# Wiznet-W5500.net
KiCad netlist of a schematic drawn in EAGLE
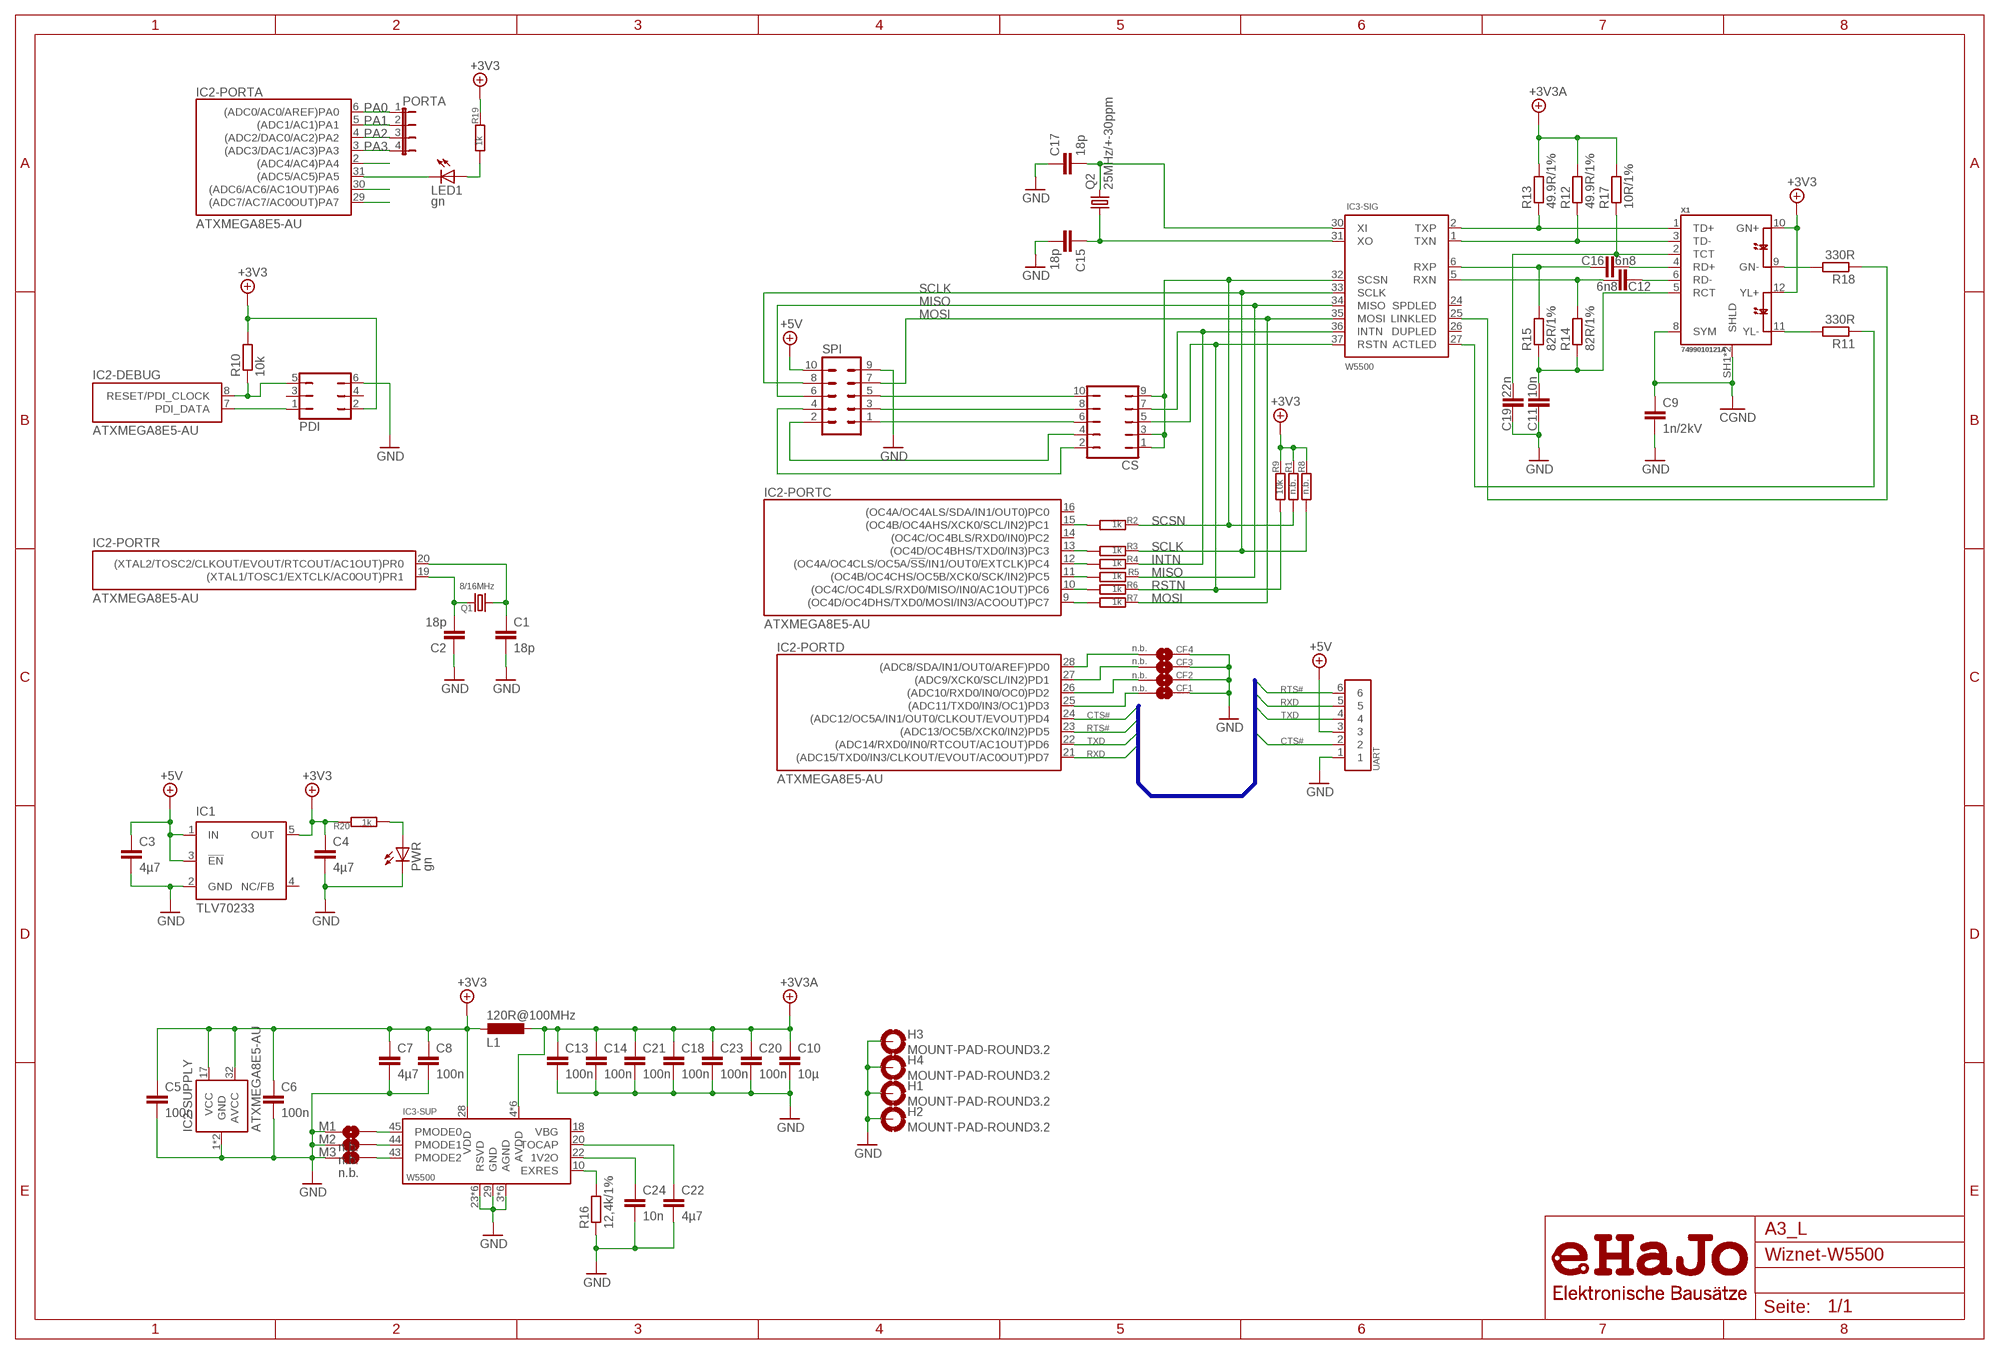
[diagram p0: schematic, sheet 1]

(export (version "E")
  (design (tool "Eeschema 10.0.6"))
  (components
    (comp (ref "C1")
      (value "18p")
      (footprint "eagle-import:C0603")
      (libsource (lib "eagle-import") (part "CC0603"))
    )
    (comp (ref "C2")
      (value "18p")
      (footprint "eagle-import:C0603")
      (libsource (lib "eagle-import") (part "CC0603"))
    )
    (comp (ref "C3")
      (value "4µ7")
      (footprint "eagle-import:C0805")
      (libsource (lib "eagle-import") (part "CC0805"))
    )
    (comp (ref "C4")
      (value "4µ7")
      (footprint "eagle-import:C0805")
      (libsource (lib "eagle-import") (part "CC0805"))
    )
    (comp (ref "C5")
      (value "100n")
      (footprint "eagle-import:C0603")
      (libsource (lib "eagle-import") (part "CC0603"))
    )
    (comp (ref "C6")
      (value "100n")
      (footprint "eagle-import:C0603")
      (libsource (lib "eagle-import") (part "CC0603"))
    )
    (comp (ref "C7")
      (value "4µ7")
      (footprint "eagle-import:C0805")
      (libsource (lib "eagle-import") (part "CC0805"))
    )
    (comp (ref "C8")
      (value "100n")
      (footprint "eagle-import:C0603")
      (libsource (lib "eagle-import") (part "CC0603"))
    )
    (comp (ref "C9")
      (value "1n/2kV")
      (footprint "eagle-import:C0805")
      (libsource (lib "eagle-import") (part "CC0805"))
    )
    (comp (ref "C10")
      (value "10µ")
      (footprint "eagle-import:C1206")
      (libsource (lib "eagle-import") (part "CC1206"))
    )
    (comp (ref "C11")
      (value "10n")
      (footprint "eagle-import:C0603")
      (libsource (lib "eagle-import") (part "CC0603"))
    )
    (comp (ref "C12")
      (value "6n8")
      (footprint "eagle-import:C0603")
      (libsource (lib "eagle-import") (part "CC0603"))
    )
    (comp (ref "C13")
      (value "100n")
      (footprint "eagle-import:C0603")
      (libsource (lib "eagle-import") (part "CC0603"))
    )
    (comp (ref "C14")
      (value "100n")
      (footprint "eagle-import:C0603")
      (libsource (lib "eagle-import") (part "CC0603"))
    )
    (comp (ref "C15")
      (value "18p")
      (footprint "eagle-import:C0603")
      (libsource (lib "eagle-import") (part "CC0603"))
    )
    (comp (ref "C16")
      (value "6n8")
      (footprint "eagle-import:C0603")
      (libsource (lib "eagle-import") (part "CC0603"))
    )
    (comp (ref "C17")
      (value "18p")
      (footprint "eagle-import:C0603")
      (libsource (lib "eagle-import") (part "CC0603"))
    )
    (comp (ref "C18")
      (value "100n")
      (footprint "eagle-import:C0603")
      (libsource (lib "eagle-import") (part "CC0603"))
    )
    (comp (ref "C19")
      (value "22n")
      (footprint "eagle-import:C0603")
      (libsource (lib "eagle-import") (part "CC0603"))
    )
    (comp (ref "C20")
      (value "100n")
      (footprint "eagle-import:C0603")
      (libsource (lib "eagle-import") (part "CC0603"))
    )
    (comp (ref "C21")
      (value "100n")
      (footprint "eagle-import:C0603")
      (libsource (lib "eagle-import") (part "CC0603"))
    )
    (comp (ref "C22")
      (value "4µ7")
      (footprint "eagle-import:C0805")
      (libsource (lib "eagle-import") (part "CC0805"))
    )
    (comp (ref "C23")
      (value "100n")
      (footprint "eagle-import:C0603")
      (libsource (lib "eagle-import") (part "CC0603"))
    )
    (comp (ref "C24")
      (value "10n")
      (footprint "eagle-import:C0603")
      (libsource (lib "eagle-import") (part "CC0603"))
    )
    (comp (ref "CF1")
      (value "n.b.")
      (footprint "eagle-import:SJS")
      (libsource (lib "eagle-import") (part "SJS"))
    )
    (comp (ref "CF2")
      (value "n.b.")
      (footprint "eagle-import:SJS")
      (libsource (lib "eagle-import") (part "SJS"))
    )
    (comp (ref "CF3")
      (value "n.b.")
      (footprint "eagle-import:SJS")
      (libsource (lib "eagle-import") (part "SJS"))
    )
    (comp (ref "CF4")
      (value "n.b.")
      (footprint "eagle-import:SJS")
      (libsource (lib "eagle-import") (part "SJS"))
    )
    (comp (ref "CS")
      (value "JP5Q")
      (footprint "eagle-import:JP5Q")
      (libsource (lib "eagle-import") (part "JP5Q"))
    )
    (comp (ref "H1")
      (value "MOUNT-PAD-ROUND3.2")
      (footprint "eagle-import:3,2-PAD")
      (libsource (lib "eagle-import") (part "MOUNT-PAD-ROUND3.2"))
    )
    (comp (ref "H2")
      (value "MOUNT-PAD-ROUND3.2")
      (footprint "eagle-import:3,2-PAD")
      (libsource (lib "eagle-import") (part "MOUNT-PAD-ROUND3.2"))
    )
    (comp (ref "H3")
      (value "MOUNT-PAD-ROUND3.2")
      (footprint "eagle-import:3,2-PAD")
      (libsource (lib "eagle-import") (part "MOUNT-PAD-ROUND3.2"))
    )
    (comp (ref "H4")
      (value "MOUNT-PAD-ROUND3.2")
      (footprint "eagle-import:3,2-PAD")
      (libsource (lib "eagle-import") (part "MOUNT-PAD-ROUND3.2"))
    )
    (comp (ref "IC1")
      (value "TLV70233")
      (footprint "eagle-import:SOT23-DBV")
      (libsource (lib "eagle-import") (part "TPS77001"))
    )
    (comp (ref "IC2")
      (value "ATXMEGA8E5-AU")
      (footprint "eagle-import:TQFP32-08")
      (libsource (lib "eagle-import") (part "ATXMEGAE5-AU"))
    )
    (comp (ref "IC3")
      (value "W5500")
      (footprint "eagle-import:LQFP48")
      (libsource (lib "eagle-import") (part "W5500"))
    )
    (comp (ref "L1")
      (value "120R@100MHz")
      (footprint "eagle-import:R0805")
      (libsource (lib "eagle-import") (part "L0805"))
    )
    (comp (ref "LED1")
      (value "gn")
      (footprint "eagle-import:CHIP-LED0805")
      (libsource (lib "eagle-import") (part "LEDCHIP-LED0805"))
    )
    (comp (ref "M1")
      (value "n.b.")
      (footprint "eagle-import:SJS")
      (libsource (lib "eagle-import") (part "SJS"))
    )
    (comp (ref "M2")
      (value "n.b.")
      (footprint "eagle-import:SJS")
      (libsource (lib "eagle-import") (part "SJS"))
    )
    (comp (ref "M3")
      (value "n.b.")
      (footprint "eagle-import:SJS")
      (libsource (lib "eagle-import") (part "SJS"))
    )
    (comp (ref "PDI")
      (value "JP3Q")
      (footprint "eagle-import:JP3Q")
      (libsource (lib "eagle-import") (part "JP3Q"))
    )
    (comp (ref "PORTA")
      (value "JP4ESML")
      (footprint "eagle-import:4SML")
      (libsource (lib "eagle-import") (part "JP4ESML"))
    )
    (comp (ref "PWR")
      (value "gn")
      (footprint "eagle-import:CHIP-LED0805")
      (libsource (lib "eagle-import") (part "LEDCHIP-LED0805"))
    )
    (comp (ref "Q1")
      (value "8/16MHz")
      (footprint "eagle-import:HC49U70")
      (libsource (lib "eagle-import") (part "CRYSTALHC49U70"))
    )
    (comp (ref "Q2")
      (value "25MHz/+-30ppm")
      (footprint "eagle-import:HC49U70")
      (libsource (lib "eagle-import") (part "CRYSTALHC49U70"))
    )
    (comp (ref "R1")
      (value "n.b.")
      (footprint "eagle-import:R0603")
      (libsource (lib "eagle-import") (part "RR0603"))
    )
    (comp (ref "R2")
      (value "1k")
      (footprint "eagle-import:R0603")
      (libsource (lib "eagle-import") (part "RR0603"))
    )
    (comp (ref "R3")
      (value "1k")
      (footprint "eagle-import:R0603")
      (libsource (lib "eagle-import") (part "RR0603"))
    )
    (comp (ref "R4")
      (value "1k")
      (footprint "eagle-import:R0603")
      (libsource (lib "eagle-import") (part "RR0603"))
    )
    (comp (ref "R5")
      (value "1k")
      (footprint "eagle-import:R0603")
      (libsource (lib "eagle-import") (part "RR0603"))
    )
    (comp (ref "R6")
      (value "1k")
      (footprint "eagle-import:R0603")
      (libsource (lib "eagle-import") (part "RR0603"))
    )
    (comp (ref "R7")
      (value "1k")
      (footprint "eagle-import:R0603")
      (libsource (lib "eagle-import") (part "RR0603"))
    )
    (comp (ref "R8")
      (value "n.b.")
      (footprint "eagle-import:R0603")
      (libsource (lib "eagle-import") (part "RR0603"))
    )
    (comp (ref "R9")
      (value "10k")
      (footprint "eagle-import:R0603")
      (libsource (lib "eagle-import") (part "RR0603"))
    )
    (comp (ref "R10")
      (value "10k")
      (footprint "eagle-import:R0603")
      (libsource (lib "eagle-import") (part "RR0603"))
    )
    (comp (ref "R11")
      (value "330R")
      (footprint "eagle-import:R0603")
      (libsource (lib "eagle-import") (part "RR0603"))
    )
    (comp (ref "R12")
      (value "49.9R/1%")
      (footprint "eagle-import:R0603")
      (libsource (lib "eagle-import") (part "RR0603"))
    )
    (comp (ref "R13")
      (value "49.9R/1%")
      (footprint "eagle-import:R0603")
      (libsource (lib "eagle-import") (part "RR0603"))
    )
    (comp (ref "R14")
      (value "82R/1%")
      (footprint "eagle-import:R0603")
      (libsource (lib "eagle-import") (part "RR0603"))
    )
    (comp (ref "R15")
      (value "82R/1%")
      (footprint "eagle-import:R0603")
      (libsource (lib "eagle-import") (part "RR0603"))
    )
    (comp (ref "R16")
      (value "12,4k/1%")
      (footprint "eagle-import:R0603")
      (libsource (lib "eagle-import") (part "RR0603"))
    )
    (comp (ref "R17")
      (value "10R/1%")
      (footprint "eagle-import:R0603")
      (libsource (lib "eagle-import") (part "RR0603"))
    )
    (comp (ref "R18")
      (value "330R")
      (footprint "eagle-import:R0603")
      (libsource (lib "eagle-import") (part "RR0603"))
    )
    (comp (ref "R19")
      (value "1k")
      (footprint "eagle-import:R0603")
      (libsource (lib "eagle-import") (part "RR0603"))
    )
    (comp (ref "R20")
      (value "1k")
      (footprint "eagle-import:R0603")
      (libsource (lib "eagle-import") (part "RR0603"))
    )
    (comp (ref "SPI")
      (value "ML10")
      (footprint "eagle-import:ML10")
      (libsource (lib "eagle-import") (part "ML10"))
    )
    (comp (ref "UART")
      (value "JP6E")
      (footprint "eagle-import:JP6E")
      (libsource (lib "eagle-import") (part "JP6E"))
    )
    (comp (ref "X1")
      (value "7499010121A")
      (footprint "eagle-import:121A")
      (libsource (lib "eagle-import") (part "7499010121"))
    )
  )
  (nets
    (net (code "1") (name "+3V3") (class "Default")
      (node (ref "C4") (pin "1") (pinfunction "1_1") (pintype "passive"))
      (node (ref "C5") (pin "1") (pinfunction "1_1") (pintype "passive"))
      (node (ref "C6") (pin "1") (pinfunction "1_1") (pintype "passive"))
      (node (ref "C7") (pin "1") (pinfunction "1_1") (pintype "passive"))
      (node (ref "C8") (pin "1") (pinfunction "1_1") (pintype "passive"))
      (node (ref "IC1") (pin "5") (pinfunction "OUT_5") (pintype "passive"))
      (node (ref "IC2") (pin "17") (pinfunction "VCC_17") (pintype "bidirectional"))
      (node (ref "IC2") (pin "32") (pinfunction "AVCC_32") (pintype "bidirectional"))
      (node (ref "IC3") (pin "28") (pinfunction "VDD_28") (pintype "power_in"))
      (node (ref "L1") (pin "2") (pinfunction "2_2") (pintype "passive"))
      (node (ref "PDI") (pin "2") (pinfunction "2_2") (pintype "passive"))
      (node (ref "R1") (pin "2") (pinfunction "2_2") (pintype "passive"))
      (node (ref "R10") (pin "2") (pinfunction "2_2") (pintype "passive"))
      (node (ref "R19") (pin "2") (pinfunction "2_2") (pintype "passive"))
      (node (ref "R20") (pin "2") (pinfunction "2_2") (pintype "passive"))
      (node (ref "R8") (pin "2") (pinfunction "2_2") (pintype "passive"))
      (node (ref "R9") (pin "2") (pinfunction "2_2") (pintype "passive"))
      (node (ref "X1") (pin "10") (pinfunction "GN+_10") (pintype "bidirectional"))
      (node (ref "X1") (pin "12") (pinfunction "YL+_12") (pintype "bidirectional"))
    )
    (net (code "2") (name "+3V3A") (class "Default")
      (node (ref "C10") (pin "1") (pinfunction "1_1") (pintype "passive"))
      (node (ref "C13") (pin "1") (pinfunction "1_1") (pintype "passive"))
      (node (ref "C14") (pin "1") (pinfunction "1_1") (pintype "passive"))
      (node (ref "C18") (pin "1") (pinfunction "1_1") (pintype "passive"))
      (node (ref "C20") (pin "1") (pinfunction "1_1") (pintype "passive"))
      (node (ref "C21") (pin "1") (pinfunction "1_1") (pintype "passive"))
      (node (ref "C23") (pin "1") (pinfunction "1_1") (pintype "passive"))
      (node (ref "IC3") (pin "11") (pinfunction "AVDD_11") (pintype "power_in"))
      (node (ref "IC3") (pin "15") (pinfunction "AVDD_15") (pintype "power_in"))
      (node (ref "IC3") (pin "17") (pinfunction "AVDD_17") (pintype "power_in"))
      (node (ref "IC3") (pin "21") (pinfunction "AVDD_21") (pintype "power_in"))
      (node (ref "IC3") (pin "4") (pinfunction "AVDD_4") (pintype "power_in"))
      (node (ref "IC3") (pin "8") (pinfunction "AVDD_8") (pintype "power_in"))
      (node (ref "L1") (pin "1") (pinfunction "1_1") (pintype "passive"))
      (node (ref "R12") (pin "2") (pinfunction "2_2") (pintype "passive"))
      (node (ref "R13") (pin "2") (pinfunction "2_2") (pintype "passive"))
      (node (ref "R17") (pin "2") (pinfunction "2_2") (pintype "passive"))
    )
    (net (code "3") (name "+5V") (class "Default")
      (node (ref "C3") (pin "1") (pinfunction "1_1") (pintype "passive"))
      (node (ref "IC1") (pin "1") (pinfunction "IN_1") (pintype "input"))
      (node (ref "IC1") (pin "3") (pinfunction "~{EN}_3") (pintype "input"))
      (node (ref "SPI") (pin "10") (pinfunction "10_10") (pintype "passive"))
      (node (ref "UART") (pin "3") (pinfunction "3_3") (pintype "bidirectional"))
    )
    (net (code "4") (name "/CTS#") (class "Default")
      (node (ref "IC2") (pin "24") (pinfunction "(ADC12/OC5A/IN1/OUT0/CLKOUT/EVOUT)PD4_24") (pintype "bidirectional"))
      (node (ref "UART") (pin "2") (pinfunction "2_2") (pintype "bidirectional"))
    )
    (net (code "5") (name "/INTN") (class "Default")
      (node (ref "CS") (pin "7") (pinfunction "7_7") (pintype "passive"))
      (node (ref "IC3") (pin "36") (pinfunction "INTN_36") (pintype "output"))
      (node (ref "R4") (pin "1") (pinfunction "1_1") (pintype "passive"))
    )
    (net (code "6") (name "/MISO") (class "Default")
      (node (ref "IC3") (pin "34") (pinfunction "MISO_34") (pintype "output"))
      (node (ref "R5") (pin "1") (pinfunction "1_1") (pintype "passive"))
      (node (ref "SPI") (pin "6") (pinfunction "6_6") (pintype "passive"))
    )
    (net (code "7") (name "/MOSI") (class "Default")
      (node (ref "IC3") (pin "35") (pinfunction "MOSI_35") (pintype "input"))
      (node (ref "R7") (pin "1") (pinfunction "1_1") (pintype "passive"))
      (node (ref "SPI") (pin "7") (pinfunction "7_7") (pintype "passive"))
    )
    (net (code "8") (name "/PA0") (class "Default")
      (node (ref "IC2") (pin "6") (pinfunction "(ADC0/AC0/AREF)PA0_6") (pintype "bidirectional"))
      (node (ref "PORTA") (pin "1") (pinfunction "1_1") (pintype "passive"))
    )
    (net (code "9") (name "/PA1") (class "Default")
      (node (ref "IC2") (pin "5") (pinfunction "(ADC1/AC1)PA1_5") (pintype "bidirectional"))
      (node (ref "PORTA") (pin "2") (pinfunction "2_2") (pintype "passive"))
    )
    (net (code "10") (name "/PA2") (class "Default")
      (node (ref "IC2") (pin "4") (pinfunction "(ADC2/DAC0/AC2)PA2_4") (pintype "bidirectional"))
      (node (ref "PORTA") (pin "3") (pinfunction "3_3") (pintype "passive"))
    )
    (net (code "11") (name "/PA3") (class "Default")
      (node (ref "IC2") (pin "3") (pinfunction "(ADC3/DAC1/AC3)PA3_3") (pintype "bidirectional"))
      (node (ref "PORTA") (pin "4") (pinfunction "4_4") (pintype "passive"))
    )
    (net (code "12") (name "/RSTN") (class "Default")
      (node (ref "CS") (pin "5") (pinfunction "5_5") (pintype "passive"))
      (node (ref "IC3") (pin "37") (pinfunction "RSTN_37") (pintype "input"))
      (node (ref "R6") (pin "1") (pinfunction "1_1") (pintype "passive"))
      (node (ref "R9") (pin "1") (pinfunction "1_1") (pintype "passive"))
    )
    (net (code "13") (name "/RTS#") (class "Default")
      (node (ref "IC2") (pin "23") (pinfunction "(ADC13/OC5B/XCK0/IN2)PD5_23") (pintype "bidirectional"))
      (node (ref "UART") (pin "6") (pinfunction "6_6") (pintype "bidirectional"))
    )
    (net (code "14") (name "/RXD") (class "Default")
      (node (ref "IC2") (pin "21") (pinfunction "(ADC15/TXD0/IN3/CLKOUT/EVOUT/AC0OUT)PD7_21") (pintype "bidirectional"))
      (node (ref "UART") (pin "5") (pinfunction "5_5") (pintype "bidirectional"))
    )
    (net (code "15") (name "/SCLK") (class "Default")
      (node (ref "IC3") (pin "33") (pinfunction "SCLK_33") (pintype "input"))
      (node (ref "R3") (pin "1") (pinfunction "1_1") (pintype "passive"))
      (node (ref "R8") (pin "1") (pinfunction "1_1") (pintype "passive"))
      (node (ref "SPI") (pin "8") (pinfunction "8_8") (pintype "passive"))
    )
    (net (code "16") (name "/SCSN") (class "Default")
      (node (ref "CS") (pin "1") (pinfunction "1_1") (pintype "passive"))
      (node (ref "CS") (pin "3") (pinfunction "3_3") (pintype "passive"))
      (node (ref "CS") (pin "9") (pinfunction "9_9") (pintype "passive"))
      (node (ref "IC3") (pin "32") (pinfunction "SCSN_32") (pintype "input"))
      (node (ref "R1") (pin "1") (pinfunction "1_1") (pintype "passive"))
      (node (ref "R2") (pin "1") (pinfunction "1_1") (pintype "passive"))
    )
    (net (code "17") (name "/TXD") (class "Default")
      (node (ref "IC2") (pin "22") (pinfunction "(ADC14/RXD0/IN0/RTCOUT/AC1OUT)PD6_22") (pintype "bidirectional"))
      (node (ref "UART") (pin "4") (pinfunction "4_4") (pintype "bidirectional"))
    )
    (net (code "18") (name "CGND") (class "Default")
      (node (ref "C9") (pin "1") (pinfunction "1_1") (pintype "passive"))
      (node (ref "X1") (pin "8") (pinfunction "SYM_8") (pintype "bidirectional"))
      (node (ref "X1") (pin "SH1") (pinfunction "SHLD_SH1") (pintype "bidirectional"))
      (node (ref "X1") (pin "SH2") (pinfunction "SHLD_SH2") (pintype "bidirectional"))
    )
    (net (code "19") (name "GND") (class "Default")
      (node (ref "C1") (pin "2") (pinfunction "2_2") (pintype "passive"))
      (node (ref "C10") (pin "2") (pinfunction "2_2") (pintype "passive"))
      (node (ref "C11") (pin "1") (pinfunction "1_1") (pintype "passive"))
      (node (ref "C13") (pin "2") (pinfunction "2_2") (pintype "passive"))
      (node (ref "C14") (pin "2") (pinfunction "2_2") (pintype "passive"))
      (node (ref "C15") (pin "2") (pinfunction "2_2") (pintype "passive"))
      (node (ref "C17") (pin "1") (pinfunction "1_1") (pintype "passive"))
      (node (ref "C18") (pin "2") (pinfunction "2_2") (pintype "passive"))
      (node (ref "C19") (pin "1") (pinfunction "1_1") (pintype "passive"))
      (node (ref "C2") (pin "1") (pinfunction "1_1") (pintype "passive"))
      (node (ref "C20") (pin "2") (pinfunction "2_2") (pintype "passive"))
      (node (ref "C21") (pin "2") (pinfunction "2_2") (pintype "passive"))
      (node (ref "C22") (pin "2") (pinfunction "2_2") (pintype "passive"))
      (node (ref "C23") (pin "2") (pinfunction "2_2") (pintype "passive"))
      (node (ref "C24") (pin "2") (pinfunction "2_2") (pintype "passive"))
      (node (ref "C3") (pin "2") (pinfunction "2_2") (pintype "passive"))
      (node (ref "C4") (pin "2") (pinfunction "2_2") (pintype "passive"))
      (node (ref "C5") (pin "2") (pinfunction "2_2") (pintype "passive"))
      (node (ref "C6") (pin "2") (pinfunction "2_2") (pintype "passive"))
      (node (ref "C7") (pin "2") (pinfunction "2_2") (pintype "passive"))
      (node (ref "C8") (pin "2") (pinfunction "2_2") (pintype "passive"))
      (node (ref "C9") (pin "2") (pinfunction "2_2") (pintype "passive"))
      (node (ref "CF1") (pin "2") (pinfunction "2_2") (pintype "passive"))
      (node (ref "CF2") (pin "2") (pinfunction "2_2") (pintype "passive"))
      (node (ref "CF3") (pin "2") (pinfunction "2_2") (pintype "passive"))
      (node (ref "CF4") (pin "2") (pinfunction "2_2") (pintype "passive"))
      (node (ref "H1") (pin "B3,2") (pinfunction "MOUNT_B3,2") (pintype "passive"))
      (node (ref "H2") (pin "B3,2") (pinfunction "MOUNT_B3,2") (pintype "passive"))
      (node (ref "H3") (pin "B3,2") (pinfunction "MOUNT_B3,2") (pintype "passive"))
      (node (ref "H4") (pin "B3,2") (pinfunction "MOUNT_B3,2") (pintype "passive"))
      (node (ref "IC1") (pin "2") (pinfunction "GND_2") (pintype "power_in"))
      (node (ref "IC2") (pin "1") (pinfunction "GND_1") (pintype "bidirectional"))
      (node (ref "IC2") (pin "18") (pinfunction "GND_18") (pintype "bidirectional"))
      (node (ref "IC3") (pin "14") (pinfunction "AGND_14") (pintype "power_in"))
      (node (ref "IC3") (pin "16") (pinfunction "AGND_16") (pintype "power_in"))
      (node (ref "IC3") (pin "19") (pinfunction "AGND_19") (pintype "power_in"))
      (node (ref "IC3") (pin "23") (pinfunction "RSVD_23") (pintype "input"))
      (node (ref "IC3") (pin "29") (pinfunction "GND_29") (pintype "power_in"))
      (node (ref "IC3") (pin "3") (pinfunction "AGND_3") (pintype "power_in"))
      (node (ref "IC3") (pin "38") (pinfunction "RSVD_38") (pintype "input"))
      (node (ref "IC3") (pin "39") (pinfunction "RSVD_39") (pintype "input"))
      (node (ref "IC3") (pin "40") (pinfunction "RSVD_40") (pintype "input"))
      (node (ref "IC3") (pin "41") (pinfunction "RSVD_41") (pintype "input"))
      (node (ref "IC3") (pin "42") (pinfunction "RSVD_42") (pintype "input"))
      (node (ref "IC3") (pin "48") (pinfunction "AGND_48") (pintype "power_in"))
      (node (ref "IC3") (pin "9") (pinfunction "AGND_9") (pintype "power_in"))
      (node (ref "M1") (pin "1") (pinfunction "1_1") (pintype "passive"))
      (node (ref "M2") (pin "1") (pinfunction "1_1") (pintype "passive"))
      (node (ref "M3") (pin "1") (pinfunction "1_1") (pintype "passive"))
      (node (ref "PDI") (pin "6") (pinfunction "6_6") (pintype "passive"))
      (node (ref "PWR") (pin "C") (pinfunction "C_C") (pintype "passive"))
      (node (ref "R16") (pin "1") (pinfunction "1_1") (pintype "passive"))
      (node (ref "SPI") (pin "9") (pinfunction "9_9") (pintype "passive"))
      (node (ref "UART") (pin "1") (pinfunction "1_1") (pintype "bidirectional"))
    )
    (net (code "20") (name "Net-(CS-Pad2)") (class "Default")
      (node (ref "CS") (pin "2") (pinfunction "2_2") (pintype "passive"))
      (node (ref "SPI") (pin "4") (pinfunction "4_4") (pintype "passive"))
    )
    (net (code "21") (name "Net-(CS-Pad4)") (class "Default")
      (node (ref "CS") (pin "4") (pinfunction "4_4") (pintype "passive"))
      (node (ref "SPI") (pin "2") (pinfunction "2_2") (pintype "passive"))
    )
    (net (code "22") (name "Net-(CS-Pad6)") (class "Default")
      (node (ref "CS") (pin "6") (pinfunction "6_6") (pintype "passive"))
      (node (ref "SPI") (pin "1") (pinfunction "1_1") (pintype "passive"))
    )
    (net (code "23") (name "Net-(CS-Pad8)") (class "Default")
      (node (ref "CS") (pin "8") (pinfunction "8_8") (pintype "passive"))
      (node (ref "SPI") (pin "3") (pinfunction "3_3") (pintype "passive"))
    )
    (net (code "24") (name "Net-(CS-Pad10)") (class "Default")
      (node (ref "CS") (pin "10") (pinfunction "10_10") (pintype "passive"))
      (node (ref "SPI") (pin "5") (pinfunction "5_5") (pintype "passive"))
    )
    (net (code "25") (name "Net-(IC2A-PDI_DATA)") (class "Default")
      (node (ref "IC2") (pin "7") (pinfunction "PDI_DATA_7") (pintype "bidirectional"))
      (node (ref "PDI") (pin "1") (pinfunction "1_1") (pintype "passive"))
    )
    (net (code "26") (name "Net-(IC2A-RESET{slash}PDI_CLOCK)") (class "Default")
      (node (ref "IC2") (pin "8") (pinfunction "RESET/PDI_CLOCK_8") (pintype "bidirectional"))
      (node (ref "PDI") (pin "5") (pinfunction "5_5") (pintype "passive"))
      (node (ref "R10") (pin "1") (pinfunction "1_1") (pintype "passive"))
    )
    (net (code "27") (name "Net-(IC2B-(ADC5{slash}AC5)PA5)") (class "Default")
      (node (ref "IC2") (pin "31") (pinfunction "(ADC5/AC5)PA5_31") (pintype "bidirectional"))
      (node (ref "LED1") (pin "C") (pinfunction "C_C") (pintype "passive"))
    )
    (net (code "28") (name "Net-(IC2C-(OC4A{slash}OC4CLS{slash}OC5A{slash}~{SS}{slash}IN1{slash}OUT0{slash}EXTCLK)PC4)") (class "Default")
      (node (ref "IC2") (pin "12") (pinfunction "(OC4A/OC4CLS/OC5A/~{SS}/IN1/OUT0/EXTCLK)PC4_12") (pintype "bidirectional"))
      (node (ref "R4") (pin "2") (pinfunction "2_2") (pintype "passive"))
    )
    (net (code "29") (name "Net-(IC2C-(OC4B{slash}OC4AHS{slash}XCK0{slash}SCL{slash}IN2)PC1)") (class "Default")
      (node (ref "IC2") (pin "15") (pinfunction "(OC4B/OC4AHS/XCK0/SCL/IN2)PC1_15") (pintype "bidirectional"))
      (node (ref "R2") (pin "2") (pinfunction "2_2") (pintype "passive"))
    )
    (net (code "30") (name "Net-(IC2C-(OC4B{slash}OC4CHS{slash}OC5B{slash}XCK0{slash}SCK{slash}IN2)PC5)") (class "Default")
      (node (ref "IC2") (pin "11") (pinfunction "(OC4B/OC4CHS/OC5B/XCK0/SCK/IN2)PC5_11") (pintype "bidirectional"))
      (node (ref "R5") (pin "2") (pinfunction "2_2") (pintype "passive"))
    )
    (net (code "31") (name "Net-(IC2C-(OC4C{slash}OC4DLS{slash}RXD0{slash}MISO{slash}IN0{slash}AC1OUT)PC6)") (class "Default")
      (node (ref "IC2") (pin "10") (pinfunction "(OC4C/OC4DLS/RXD0/MISO/IN0/AC1OUT)PC6_10") (pintype "bidirectional"))
      (node (ref "R6") (pin "2") (pinfunction "2_2") (pintype "passive"))
    )
    (net (code "32") (name "Net-(IC2C-(OC4D{slash}OC4BHS{slash}TXD0{slash}IN3)PC3)") (class "Default")
      (node (ref "IC2") (pin "13") (pinfunction "(OC4D/OC4BHS/TXD0/IN3)PC3_13") (pintype "bidirectional"))
      (node (ref "R3") (pin "2") (pinfunction "2_2") (pintype "passive"))
    )
    (net (code "33") (name "Net-(IC2C-(OC4D{slash}OC4DHS{slash}TXD0{slash}MOSI{slash}IN3{slash}ACOOUT)PC7)") (class "Default")
      (node (ref "IC2") (pin "9") (pinfunction "(OC4D/OC4DHS/TXD0/MOSI/IN3/ACOOUT)PC7_9") (pintype "bidirectional"))
      (node (ref "R7") (pin "2") (pinfunction "2_2") (pintype "passive"))
    )
    (net (code "34") (name "Net-(IC2D-(ADC8{slash}SDA{slash}IN1{slash}OUT0{slash}AREF)PD0)") (class "Default")
      (node (ref "CF4") (pin "1") (pinfunction "1_1") (pintype "passive"))
      (node (ref "IC2") (pin "28") (pinfunction "(ADC8/SDA/IN1/OUT0/AREF)PD0_28") (pintype "bidirectional"))
    )
    (net (code "35") (name "Net-(IC2D-(ADC9{slash}XCK0{slash}SCL{slash}IN2)PD1)") (class "Default")
      (node (ref "CF3") (pin "1") (pinfunction "1_1") (pintype "passive"))
      (node (ref "IC2") (pin "27") (pinfunction "(ADC9/XCK0/SCL/IN2)PD1_27") (pintype "bidirectional"))
    )
    (net (code "36") (name "Net-(IC2D-(ADC10{slash}RXD0{slash}IN0{slash}OC0)PD2)") (class "Default")
      (node (ref "CF2") (pin "1") (pinfunction "1_1") (pintype "passive"))
      (node (ref "IC2") (pin "26") (pinfunction "(ADC10/RXD0/IN0/OC0)PD2_26") (pintype "bidirectional"))
    )
    (net (code "37") (name "Net-(IC2D-(ADC11{slash}TXD0{slash}IN3{slash}OC1)PD3)") (class "Default")
      (node (ref "CF1") (pin "1") (pinfunction "1_1") (pintype "passive"))
      (node (ref "IC2") (pin "25") (pinfunction "(ADC11/TXD0/IN3/OC1)PD3_25") (pintype "bidirectional"))
    )
    (net (code "38") (name "Net-(IC2E-(XTAL1{slash}TOSC1{slash}EXTCLK{slash}AC0OUT)PR1)") (class "Default")
      (node (ref "C2") (pin "2") (pinfunction "2_2") (pintype "passive"))
      (node (ref "IC2") (pin "19") (pinfunction "(XTAL1/TOSC1/EXTCLK/AC0OUT)PR1_19") (pintype "bidirectional"))
      (node (ref "Q1") (pin "1") (pinfunction "1_1") (pintype "passive"))
    )
    (net (code "39") (name "Net-(IC2E-(XTAL2{slash}TOSC2{slash}CLKOUT{slash}EVOUT{slash}RTCOUT{slash}AC1OUT)PR0)") (class "Default")
      (node (ref "C1") (pin "1") (pinfunction "1_1") (pintype "passive"))
      (node (ref "IC2") (pin "20") (pinfunction "(XTAL2/TOSC2/CLKOUT/EVOUT/RTCOUT/AC1OUT)PR0_20") (pintype "bidirectional"))
      (node (ref "Q1") (pin "2") (pinfunction "2_2") (pintype "passive"))
    )
    (net (code "40") (name "Net-(IC3A-ACTLED)") (class "Default")
      (node (ref "IC3") (pin "27") (pinfunction "ACTLED_27") (pintype "output"))
      (node (ref "R11") (pin "1") (pinfunction "1_1") (pintype "passive"))
    )
    (net (code "41") (name "Net-(IC3A-LINKLED)") (class "Default")
      (node (ref "IC3") (pin "25") (pinfunction "LINKLED_25") (pintype "output"))
      (node (ref "R18") (pin "1") (pinfunction "1_1") (pintype "passive"))
    )
    (net (code "42") (name "Net-(IC3A-RXN)") (class "Default")
      (node (ref "C12") (pin "2") (pinfunction "2_2") (pintype "passive"))
      (node (ref "IC3") (pin "5") (pinfunction "RXN_5") (pintype "input"))
      (node (ref "R14") (pin "2") (pinfunction "2_2") (pintype "passive"))
    )
    (net (code "43") (name "Net-(IC3A-RXP)") (class "Default")
      (node (ref "C16") (pin "1") (pinfunction "1_1") (pintype "passive"))
      (node (ref "IC3") (pin "6") (pinfunction "RXP_6") (pintype "input"))
      (node (ref "R15") (pin "2") (pinfunction "2_2") (pintype "passive"))
    )
    (net (code "44") (name "Net-(IC3A-TXN)") (class "Default")
      (node (ref "IC3") (pin "1") (pinfunction "TXN_1") (pintype "output"))
      (node (ref "R12") (pin "1") (pinfunction "1_1") (pintype "passive"))
      (node (ref "X1") (pin "3") (pinfunction "TD-_3") (pintype "bidirectional"))
    )
    (net (code "45") (name "Net-(IC3A-TXP)") (class "Default")
      (node (ref "IC3") (pin "2") (pinfunction "TXP_2") (pintype "output"))
      (node (ref "R13") (pin "1") (pinfunction "1_1") (pintype "passive"))
      (node (ref "X1") (pin "1") (pinfunction "TD+_1") (pintype "bidirectional"))
    )
    (net (code "46") (name "Net-(IC3A-XI)") (class "Default")
      (node (ref "C17") (pin "2") (pinfunction "2_2") (pintype "passive"))
      (node (ref "IC3") (pin "30") (pinfunction "XI_30") (pintype "input"))
      (node (ref "Q2") (pin "2") (pinfunction "2_2") (pintype "passive"))
    )
    (net (code "47") (name "Net-(IC3A-XO)") (class "Default")
      (node (ref "C15") (pin "1") (pinfunction "1_1") (pintype "passive"))
      (node (ref "IC3") (pin "31") (pinfunction "XO_31") (pintype "output"))
      (node (ref "Q2") (pin "1") (pinfunction "1_1") (pintype "passive"))
    )
    (net (code "48") (name "Net-(IC3B-1V2O)") (class "Default")
      (node (ref "C24") (pin "1") (pinfunction "1_1") (pintype "passive"))
      (node (ref "IC3") (pin "22") (pinfunction "1V2O_22") (pintype "output"))
    )
    (net (code "49") (name "Net-(IC3B-EXRES)") (class "Default")
      (node (ref "IC3") (pin "10") (pinfunction "EXRES_10") (pintype "bidirectional"))
      (node (ref "R16") (pin "2") (pinfunction "2_2") (pintype "passive"))
    )
    (net (code "50") (name "Net-(IC3B-PMODE0)") (class "Default")
      (node (ref "IC3") (pin "45") (pinfunction "PMODE0_45") (pintype "input"))
      (node (ref "M1") (pin "2") (pinfunction "2_2") (pintype "passive"))
    )
    (net (code "51") (name "Net-(IC3B-PMODE1)") (class "Default")
      (node (ref "IC3") (pin "44") (pinfunction "PMODE1_44") (pintype "input"))
      (node (ref "M2") (pin "2") (pinfunction "2_2") (pintype "passive"))
    )
    (net (code "52") (name "Net-(IC3B-PMODE2)") (class "Default")
      (node (ref "IC3") (pin "43") (pinfunction "PMODE2_43") (pintype "input"))
      (node (ref "M3") (pin "2") (pinfunction "2_2") (pintype "passive"))
    )
    (net (code "53") (name "Net-(IC3B-TOCAP)") (class "Default")
      (node (ref "C22") (pin "1") (pinfunction "1_1") (pintype "passive"))
      (node (ref "IC3") (pin "20") (pinfunction "TOCAP_20") (pintype "output"))
    )
    (net (code "54") (name "Net-(LED1-PadA)") (class "Default")
      (node (ref "LED1") (pin "A") (pinfunction "A_A") (pintype "passive"))
      (node (ref "R19") (pin "1") (pinfunction "1_1") (pintype "passive"))
    )
    (net (code "55") (name "Net-(PWR-PadA)") (class "Default")
      (node (ref "PWR") (pin "A") (pinfunction "A_A") (pintype "passive"))
      (node (ref "R20") (pin "1") (pinfunction "1_1") (pintype "passive"))
    )
    (net (code "56") (name "Net-(X1-GN-)") (class "Default")
      (node (ref "R18") (pin "2") (pinfunction "2_2") (pintype "passive"))
      (node (ref "X1") (pin "9") (pinfunction "GN-_9") (pintype "bidirectional"))
    )
    (net (code "57") (name "Net-(X1-RCT)") (class "Default")
      (node (ref "C11") (pin "2") (pinfunction "2_2") (pintype "passive"))
      (node (ref "R14") (pin "1") (pinfunction "1_1") (pintype "passive"))
      (node (ref "R15") (pin "1") (pinfunction "1_1") (pintype "passive"))
      (node (ref "X1") (pin "5") (pinfunction "RCT_5") (pintype "bidirectional"))
    )
    (net (code "58") (name "Net-(X1-RD+)") (class "Default")
      (node (ref "C16") (pin "2") (pinfunction "2_2") (pintype "passive"))
      (node (ref "X1") (pin "4") (pinfunction "RD+_4") (pintype "bidirectional"))
    )
    (net (code "59") (name "Net-(X1-RD-)") (class "Default")
      (node (ref "C12") (pin "1") (pinfunction "1_1") (pintype "passive"))
      (node (ref "X1") (pin "6") (pinfunction "RD-_6") (pintype "bidirectional"))
    )
    (net (code "60") (name "Net-(X1-TCT)") (class "Default")
      (node (ref "C19") (pin "2") (pinfunction "2_2") (pintype "passive"))
      (node (ref "R17") (pin "1") (pinfunction "1_1") (pintype "passive"))
      (node (ref "X1") (pin "2") (pinfunction "TCT_2") (pintype "bidirectional"))
    )
    (net (code "61") (name "Net-(X1-YL-)") (class "Default")
      (node (ref "R11") (pin "2") (pinfunction "2_2") (pintype "passive"))
      (node (ref "X1") (pin "11") (pinfunction "YL-_11") (pintype "bidirectional"))
    )
    (net (code "62") (name "unconnected-(IC1-NC{slash}FB-Pad4)") (class "Default")
      (node (ref "IC1") (pin "4") (pinfunction "NC/FB_4") (pintype "passive"))
    )
    (net (code "63") (name "unconnected-(IC2B-(ADC4{slash}AC4)PA4-Pad2)") (class "Default")
      (node (ref "IC2") (pin "2") (pinfunction "(ADC4/AC4)PA4_2") (pintype "bidirectional"))
    )
    (net (code "64") (name "unconnected-(IC2B-(ADC6{slash}AC6{slash}AC1OUT)PA6-Pad30)") (class "Default")
      (node (ref "IC2") (pin "30") (pinfunction "(ADC6/AC6/AC1OUT)PA6_30") (pintype "bidirectional"))
    )
    (net (code "65") (name "unconnected-(IC2B-(ADC7{slash}AC7{slash}AC0OUT)PA7-Pad29)") (class "Default")
      (node (ref "IC2") (pin "29") (pinfunction "(ADC7/AC7/AC0OUT)PA7_29") (pintype "bidirectional"))
    )
    (net (code "66") (name "unconnected-(IC2C-(OC4A{slash}OC4ALS{slash}SDA{slash}IN1{slash}OUT0)PC0-Pad16)") (class "Default")
      (node (ref "IC2") (pin "16") (pinfunction "(OC4A/OC4ALS/SDA/IN1/OUT0)PC0_16") (pintype "bidirectional"))
    )
    (net (code "67") (name "unconnected-(IC2C-(OC4C{slash}OC4BLS{slash}RXD0{slash}IN0)PC2-Pad14)") (class "Default")
      (node (ref "IC2") (pin "14") (pinfunction "(OC4C/OC4BLS/RXD0/IN0)PC2_14") (pintype "bidirectional"))
    )
    (net (code "68") (name "unconnected-(IC3A-DUPLED-Pad26)") (class "Default")
      (node (ref "IC3") (pin "26") (pinfunction "DUPLED_26") (pintype "output"))
    )
    (net (code "69") (name "unconnected-(IC3A-SPDLED-Pad24)") (class "Default")
      (node (ref "IC3") (pin "24") (pinfunction "SPDLED_24") (pintype "output"))
    )
    (net (code "70") (name "unconnected-(IC3B-VBG-Pad18)") (class "Default")
      (node (ref "IC3") (pin "18") (pinfunction "VBG_18") (pintype "output"))
    )
    (net (code "71") (name "unconnected-(PDI-Pad3)") (class "Default")
      (node (ref "PDI") (pin "3") (pinfunction "3_3") (pintype "passive"))
    )
    (net (code "72") (name "unconnected-(PDI-Pad4)") (class "Default")
      (node (ref "PDI") (pin "4") (pinfunction "4_4") (pintype "passive"))
    )
  )
)
